# sensor.net
KiCad netlist of a schematic drawn in EAGLE
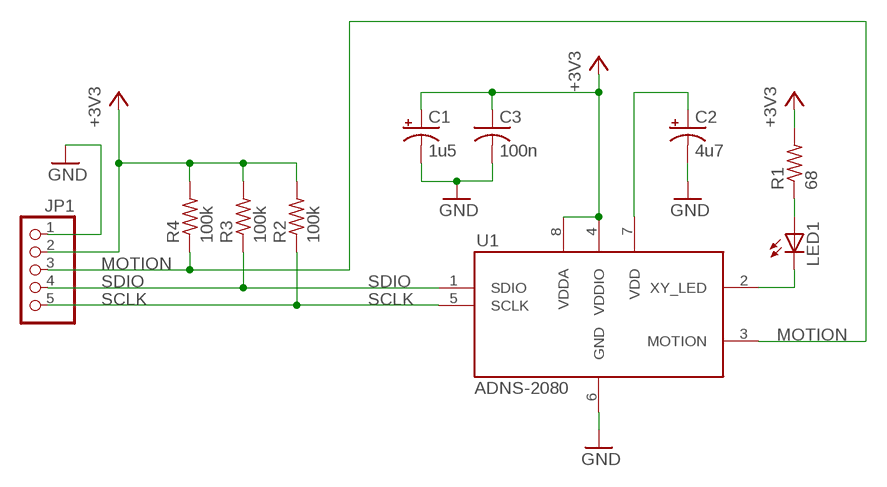
[diagram p0: schematic, sheet 1]

(export (version "E")
  (design (tool "Eeschema 10.0.6"))
  (components
    (comp (ref "C1")
      (value "1u5")
      (footprint "eagle-import:E2,5-5")
      (libsource (lib "eagle-import") (part "CPOL-USE2.5-5"))
    )
    (comp (ref "C2")
      (value "4u7")
      (footprint "eagle-import:E2,5-5")
      (libsource (lib "eagle-import") (part "CPOL-USE2.5-5"))
    )
    (comp (ref "C3")
      (value "100n")
      (footprint "eagle-import:C025-025X050")
      (libsource (lib "eagle-import") (part "C-US025-025X050"))
    )
    (comp (ref "JP1")
      (value "PINHD-1X5")
      (footprint "eagle-import:1X05")
      (libsource (lib "eagle-import") (part "PINHD-1X5"))
    )
    (comp (ref "LED1")
      (value "LED5MM")
      (footprint "eagle-import:LED5MM")
      (libsource (lib "eagle-import") (part "LED5MM"))
    )
    (comp (ref "R1")
      (value "68")
      (footprint "eagle-import:0207_7")
      (libsource (lib "eagle-import") (part "R-US_0207/7"))
    )
    (comp (ref "R2")
      (value "100k")
      (footprint "eagle-import:0204_5")
      (libsource (lib "eagle-import") (part "R-US_0204/5"))
    )
    (comp (ref "R3")
      (value "100k")
      (footprint "eagle-import:0204_5")
      (libsource (lib "eagle-import") (part "R-US_0204/5"))
    )
    (comp (ref "R4")
      (value "100k")
      (footprint "eagle-import:0204_5")
      (libsource (lib "eagle-import") (part "R-US_0204/5"))
    )
    (comp (ref "U1")
      (value "ADNS-2080")
      (footprint "eagle-import:DIP8-OPTICAL")
      (libsource (lib "eagle-import") (part "ADNS-2080"))
    )
  )
  (nets
    (net (code "1") (name "+3V3") (class "Default")
      (node (ref "C1") (pin "+") (pinfunction "+_+") (pintype "passive"))
      (node (ref "C3") (pin "1") (pinfunction "1_1") (pintype "passive"))
      (node (ref "JP1") (pin "2") (pinfunction "2_2") (pintype "passive"))
      (node (ref "R1") (pin "2") (pinfunction "2_2") (pintype "passive"))
      (node (ref "R2") (pin "2") (pinfunction "2_2") (pintype "passive"))
      (node (ref "R3") (pin "2") (pinfunction "2_2") (pintype "passive"))
      (node (ref "R4") (pin "2") (pinfunction "2_2") (pintype "passive"))
      (node (ref "U1") (pin "4") (pinfunction "VDDIO_4") (pintype "passive"))
      (node (ref "U1") (pin "8") (pinfunction "VDDA_8") (pintype "passive"))
    )
    (net (code "2") (name "/MOTION") (class "Default")
      (node (ref "JP1") (pin "3") (pinfunction "3_3") (pintype "passive"))
      (node (ref "R4") (pin "1") (pinfunction "1_1") (pintype "passive"))
      (node (ref "U1") (pin "3") (pinfunction "MOTION_3") (pintype "output"))
    )
    (net (code "3") (name "/SCLK") (class "Default")
      (node (ref "JP1") (pin "5") (pinfunction "5_5") (pintype "passive"))
      (node (ref "R2") (pin "1") (pinfunction "1_1") (pintype "passive"))
      (node (ref "U1") (pin "5") (pinfunction "SCLK_5") (pintype "input"))
    )
    (net (code "4") (name "/SDIO") (class "Default")
      (node (ref "JP1") (pin "4") (pinfunction "4_4") (pintype "passive"))
      (node (ref "R3") (pin "1") (pinfunction "1_1") (pintype "passive"))
      (node (ref "U1") (pin "1") (pinfunction "SDIO_1") (pintype "tri_state"))
    )
    (net (code "5") (name "GND") (class "Default")
      (node (ref "C1") (pin "-") (pinfunction "-_-") (pintype "passive"))
      (node (ref "C2") (pin "-") (pinfunction "-_-") (pintype "passive"))
      (node (ref "C3") (pin "2") (pinfunction "2_2") (pintype "passive"))
      (node (ref "JP1") (pin "1") (pinfunction "1_1") (pintype "passive"))
      (node (ref "U1") (pin "6") (pinfunction "GND_6") (pintype "passive"))
    )
    (net (code "6") (name "Net-(LED1-C)") (class "Default")
      (node (ref "LED1") (pin "K") (pinfunction "C_K") (pintype "passive"))
      (node (ref "U1") (pin "2") (pinfunction "XY_LED_2") (pintype "passive"))
    )
    (net (code "7") (name "Net-(LED1-PadA)") (class "Default")
      (node (ref "LED1") (pin "A") (pinfunction "A_A") (pintype "passive"))
      (node (ref "R1") (pin "1") (pinfunction "1_1") (pintype "passive"))
    )
    (net (code "8") (name "Net-(U1-VDD)") (class "Default")
      (node (ref "C2") (pin "+") (pinfunction "+_+") (pintype "passive"))
      (node (ref "U1") (pin "7") (pinfunction "VDD_7") (pintype "passive"))
    )
  )
)
